# MCU.net
KiCad netlist of a schematic drawn in Altium Designer
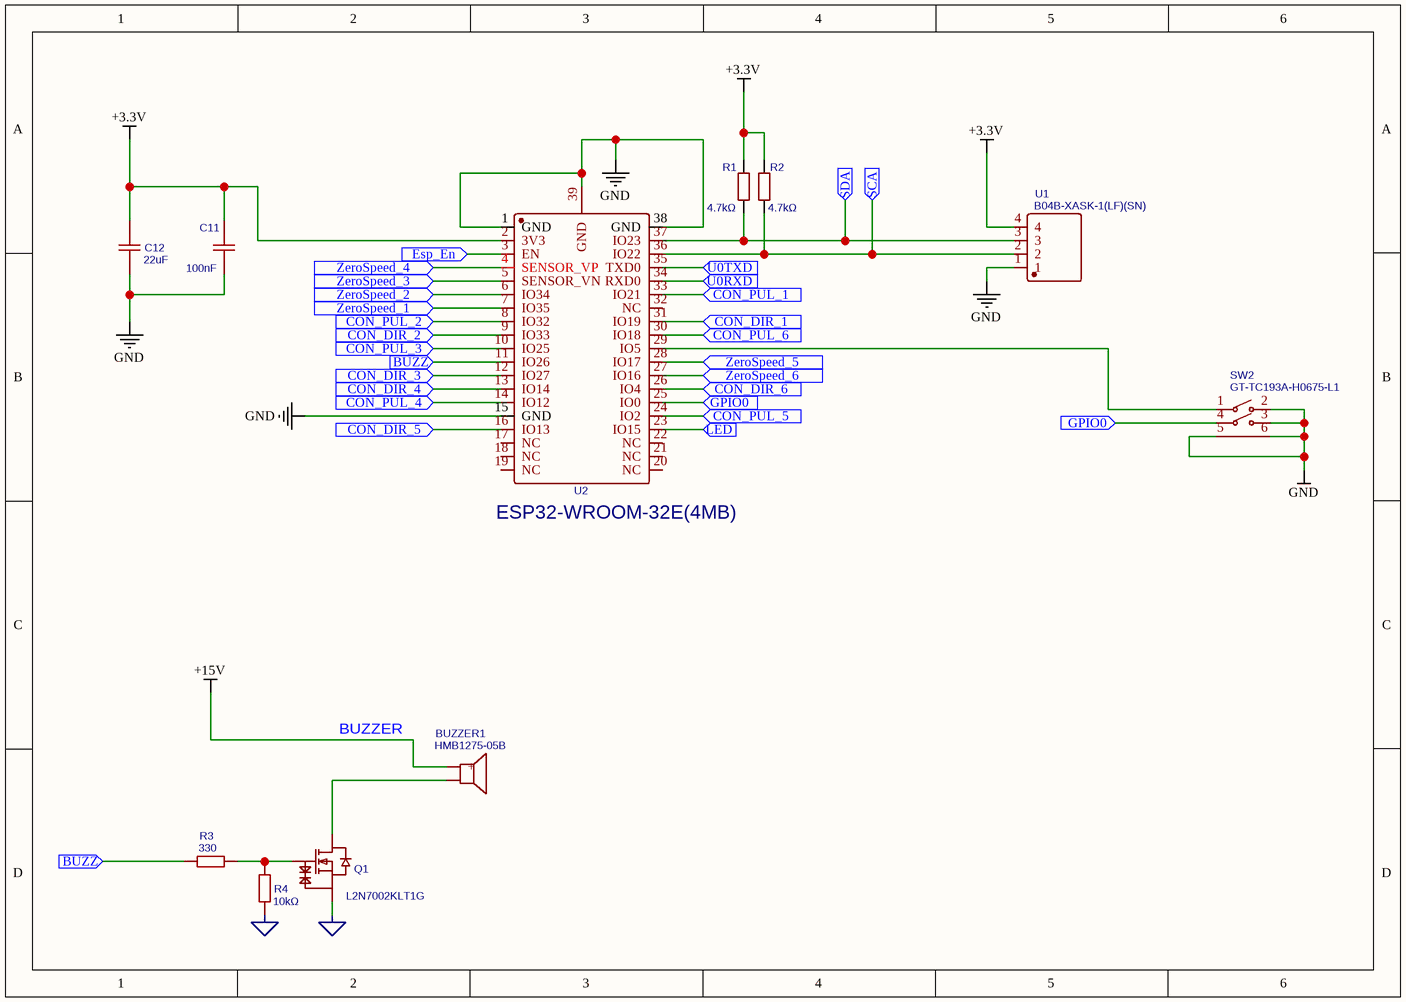
[diagram p0: MCU.schdoc]

(export (version "E")
  (design (tool "Eeschema 10.0.6"))
  (components
    (comp (ref "BUZZER1")
      (value "HMB1275-05B")
      (fields (field (name "MANUFACTURER") "HNDZ"))
      (libsource (lib "altium-import") (part "root_0_HMB1275-05B_"))
    )
    (comp (ref "C11")
      (value "100nF")
      (fields
        (field (name "MANUFACTURER") "YAGEO")
        (field (name "MANUFACTURER PART") "CC0805KRX7R8BB104")
        (field (name "CONTRIBUTOR") "LCSC")
      )
      (libsource (lib "altium-import") (part "root_1_100nF_"))
    )
    (comp (ref "C12")
      (value "22uF")
      (fields (field (name "MANUFACTURER") "SAMSUNG") (field (name "MANUFACTURER PART") "CL21A226KQQNNNE"))
      (libsource (lib "altium-import") (part "root_1_22uF_"))
    )
    (comp (ref "Q1")
      (value "L2N7002KLT1G")
      (fields (field (name "MANUFACTURER") "LRC") (field (name "MANUFACTURER PART") "L2N7002SLT1G"))
      (libsource (lib "altium-import") (part "root_0_L2N7002KLT1G_"))
    )
    (comp (ref "R1")
      (value "4.7kΩ")
      (fields (field (name "MANUFACTURER") "UniOhm") (field (name "MANUFACTURER PART") "0805W8J0472T5E"))
      (libsource (lib "altium-import") (part "root_1_4.7kΩ_"))
    )
    (comp (ref "R2")
      (value "4.7kΩ")
      (fields (field (name "MANUFACTURER") "UniOhm") (field (name "MANUFACTURER PART") "0805W8J0472T5E"))
      (libsource (lib "altium-import") (part "root_1_4.7kΩ_"))
    )
    (comp (ref "R3")
      (value "330")
      (fields
        (field (name "MANUFACTURER") "YAGEO")
        (field (name "MANUFACTURER PART") "AC0805FR-07330RL")
        (field (name "CONTRIBUTOR") "LCSC")
      )
      (libsource (lib "altium-import") (part "root_2_330_"))
    )
    (comp (ref "R4")
      (value "10kΩ")
      (fields
        (field (name "MANUFACTURER") "Ever Ohms Tech")
        (field (name "MANUFACTURER PART") "TR0805D10KP0550")
        (field (name "CONTRIBUTOR") "LCSC")
      )
      (libsource (lib "altium-import") (part "root_1_10kΩ_"))
    )
    (comp (ref "SW2")
      (value "GT-TC193A-H0675-L1")
      (fields (field (name "MANUFACTURER") "G-Switch(品赞)") (field (name "CONTRIBUTOR") "LCSC"))
      (libsource (lib "altium-import") (part "root_0_GT-TC193A-H0675-L1_"))
    )
    (comp (ref "U1")
      (value "B04B-XASK-1(LF)(SN)")
      (fields (field (name "MANUFACTURER") "JST Sales America") (field (name "CONTRIBUTOR") "LCSC"))
      (libsource (lib "altium-import") (part "root_0_B04B-XASK-1(LF)(SN)_"))
    )
    (comp (ref "U2")
      (value "ESP32-WROOM-32E(4MB)")
      (fields (field (name "MANUFACTURER") "Espressif Systems") (field (name "CONTRIBUTOR") "LCSC"))
      (libsource (lib "altium-import") (part "root_0_ESP32-WROOM-32E(4MB)_"))
    )
  )
  (nets
    (net (code "1") (name "+3.3V") (class "Default")
      (node (ref "C11") (pin "2") (pinfunction "2_2") (pintype "passive"))
      (node (ref "C12") (pin "2") (pinfunction "2_2") (pintype "passive"))
      (node (ref "R1") (pin "2") (pinfunction "2_2") (pintype "passive"))
      (node (ref "R2") (pin "2") (pinfunction "2_2") (pintype "passive"))
      (node (ref "U1") (pin "4") (pinfunction "4_4") (pintype "passive"))
      (node (ref "U2") (pin "2") (pinfunction "3V3_2") (pintype "passive"))
    )
    (net (code "2") (name "+15V") (class "Default")
      (node (ref "BUZZER1") (pin "1") (pinfunction "+_1") (pintype "passive"))
    )
    (net (code "3") (name "/BUZZ") (class "Default")
      (node (ref "R3") (pin "2") (pinfunction "2_2") (pintype "passive"))
      (node (ref "U2") (pin "11") (pinfunction "IO26_11") (pintype "passive"))
    )
    (net (code "4") (name "/CON_DIR_1") (class "Default")
      (node (ref "U2") (pin "31") (pinfunction "IO19_31") (pintype "passive"))
    )
    (net (code "5") (name "/CON_DIR_2") (class "Default")
      (node (ref "U2") (pin "9") (pinfunction "IO33_9") (pintype "passive"))
    )
    (net (code "6") (name "/CON_DIR_3") (class "Default")
      (node (ref "U2") (pin "12") (pinfunction "IO27_12") (pintype "passive"))
    )
    (net (code "7") (name "/CON_DIR_4") (class "Default")
      (node (ref "U2") (pin "13") (pinfunction "IO14_13") (pintype "passive"))
    )
    (net (code "8") (name "/CON_DIR_5") (class "Default")
      (node (ref "U2") (pin "16") (pinfunction "IO13_16") (pintype "passive"))
    )
    (net (code "9") (name "/CON_DIR_6") (class "Default")
      (node (ref "U2") (pin "26") (pinfunction "IO4_26") (pintype "passive"))
    )
    (net (code "10") (name "/CON_PUL_1") (class "Default")
      (node (ref "U2") (pin "33") (pinfunction "IO21_33") (pintype "passive"))
    )
    (net (code "11") (name "/CON_PUL_2") (class "Default")
      (node (ref "U2") (pin "8") (pinfunction "IO32_8") (pintype "passive"))
    )
    (net (code "12") (name "/CON_PUL_3") (class "Default")
      (node (ref "U2") (pin "10") (pinfunction "IO25_10") (pintype "passive"))
    )
    (net (code "13") (name "/CON_PUL_4") (class "Default")
      (node (ref "U2") (pin "14") (pinfunction "IO12_14") (pintype "passive"))
    )
    (net (code "14") (name "/CON_PUL_5") (class "Default")
      (node (ref "U2") (pin "24") (pinfunction "IO2_24") (pintype "passive"))
    )
    (net (code "15") (name "/CON_PUL_6") (class "Default")
      (node (ref "U2") (pin "30") (pinfunction "IO18_30") (pintype "passive"))
    )
    (net (code "16") (name "/Esp_En") (class "Default")
      (node (ref "U2") (pin "3") (pinfunction "EN_3") (pintype "passive"))
    )
    (net (code "17") (name "/GPIO0") (class "Default")
      (node (ref "SW2") (pin "4") (pinfunction "c_4") (pintype "passive"))
      (node (ref "U2") (pin "25") (pinfunction "IO0_25") (pintype "passive"))
    )
    (net (code "18") (name "/LED") (class "Default")
      (node (ref "U2") (pin "23") (pinfunction "IO15_23") (pintype "passive"))
    )
    (net (code "19") (name "/SCA") (class "Default")
      (node (ref "R2") (pin "1") (pinfunction "1_1") (pintype "passive"))
      (node (ref "U1") (pin "2") (pinfunction "2_2") (pintype "passive"))
      (node (ref "U2") (pin "36") (pinfunction "IO22_36") (pintype "passive"))
    )
    (net (code "20") (name "/SDA") (class "Default")
      (node (ref "R1") (pin "1") (pinfunction "1_1") (pintype "passive"))
      (node (ref "U1") (pin "3") (pinfunction "3_3") (pintype "passive"))
      (node (ref "U2") (pin "37") (pinfunction "IO23_37") (pintype "passive"))
    )
    (net (code "21") (name "/U0RXD") (class "Default")
      (node (ref "U2") (pin "34") (pinfunction "RXD0_34") (pintype "passive"))
    )
    (net (code "22") (name "/U0TXD") (class "Default")
      (node (ref "U2") (pin "35") (pinfunction "TXD0_35") (pintype "passive"))
    )
    (net (code "23") (name "/ZeroSpeed_1") (class "Default")
      (node (ref "U2") (pin "7") (pinfunction "IO35_7") (pintype "passive"))
    )
    (net (code "24") (name "/ZeroSpeed_2") (class "Default")
      (node (ref "U2") (pin "6") (pinfunction "IO34_6") (pintype "passive"))
    )
    (net (code "25") (name "/ZeroSpeed_3") (class "Default")
      (node (ref "U2") (pin "5") (pinfunction "SENSOR_VN_5") (pintype "passive"))
    )
    (net (code "26") (name "/ZeroSpeed_4") (class "Default")
      (node (ref "U2") (pin "4") (pinfunction "SENSOR_VP_4") (pintype "passive"))
    )
    (net (code "27") (name "/ZeroSpeed_5") (class "Default")
      (node (ref "U2") (pin "28") (pinfunction "IO17_28") (pintype "passive"))
    )
    (net (code "28") (name "/ZeroSpeed_6") (class "Default")
      (node (ref "U2") (pin "27") (pinfunction "IO16_27") (pintype "passive"))
    )
    (net (code "29") (name "GND") (class "Default")
      (node (ref "C11") (pin "1") (pinfunction "1_1") (pintype "passive"))
      (node (ref "C12") (pin "1") (pinfunction "1_1") (pintype "passive"))
      (node (ref "Q1") (pin "2") (pinfunction "S_2") (pintype "passive"))
      (node (ref "R4") (pin "1") (pinfunction "1_1") (pintype "passive"))
      (node (ref "SW2") (pin "2") (pinfunction "b_2") (pintype "passive"))
      (node (ref "SW2") (pin "3") (pinfunction "d_3") (pintype "passive"))
      (node (ref "SW2") (pin "5") (pinfunction "5_5") (pintype "passive"))
      (node (ref "SW2") (pin "6") (pinfunction "6_6") (pintype "passive"))
      (node (ref "U1") (pin "1") (pinfunction "1_1") (pintype "passive"))
      (node (ref "U2") (pin "1") (pinfunction "GND_1") (pintype "passive"))
      (node (ref "U2") (pin "15") (pinfunction "GND_15") (pintype "passive"))
      (node (ref "U2") (pin "38") (pinfunction "GND_38") (pintype "passive"))
      (node (ref "U2") (pin "39") (pinfunction "GND_39") (pintype "passive"))
    )
    (net (code "30") (name "Net-(Q1-D)") (class "Default")
      (node (ref "BUZZER1") (pin "2") (pinfunction "2_2") (pintype "passive"))
      (node (ref "Q1") (pin "3") (pinfunction "D_3") (pintype "passive"))
    )
    (net (code "31") (name "Net-(Q1-G)") (class "Default")
      (node (ref "Q1") (pin "1") (pinfunction "G_1") (pintype "passive"))
      (node (ref "R3") (pin "1") (pinfunction "1_1") (pintype "passive"))
      (node (ref "R4") (pin "2") (pinfunction "2_2") (pintype "passive"))
    )
    (net (code "32") (name "Net-(SW2-a)") (class "Default")
      (node (ref "SW2") (pin "1") (pinfunction "a_1") (pintype "passive"))
      (node (ref "U2") (pin "29") (pinfunction "IO5_29") (pintype "passive"))
    )
    (net (code "33") (name "unconnected-(U2-NC-Pad17)") (class "Default")
      (node (ref "U2") (pin "17") (pinfunction "NC_17") (pintype "passive"))
    )
    (net (code "34") (name "unconnected-(U2-NC-Pad18)") (class "Default")
      (node (ref "U2") (pin "18") (pinfunction "NC_18") (pintype "passive"))
    )
    (net (code "35") (name "unconnected-(U2-NC-Pad19)") (class "Default")
      (node (ref "U2") (pin "19") (pinfunction "NC_19") (pintype "passive"))
    )
    (net (code "36") (name "unconnected-(U2-NC-Pad20)") (class "Default")
      (node (ref "U2") (pin "20") (pinfunction "NC_20") (pintype "passive"))
    )
    (net (code "37") (name "unconnected-(U2-NC-Pad21)") (class "Default")
      (node (ref "U2") (pin "21") (pinfunction "NC_21") (pintype "passive"))
    )
    (net (code "38") (name "unconnected-(U2-NC-Pad22)") (class "Default")
      (node (ref "U2") (pin "22") (pinfunction "NC_22") (pintype "passive"))
    )
    (net (code "39") (name "unconnected-(U2-NC-Pad32)") (class "Default")
      (node (ref "U2") (pin "32") (pinfunction "NC_32") (pintype "passive"))
    )
  )
)
